# eagle_exp_3.net
KiCad netlist of a schematic drawn in EAGLE
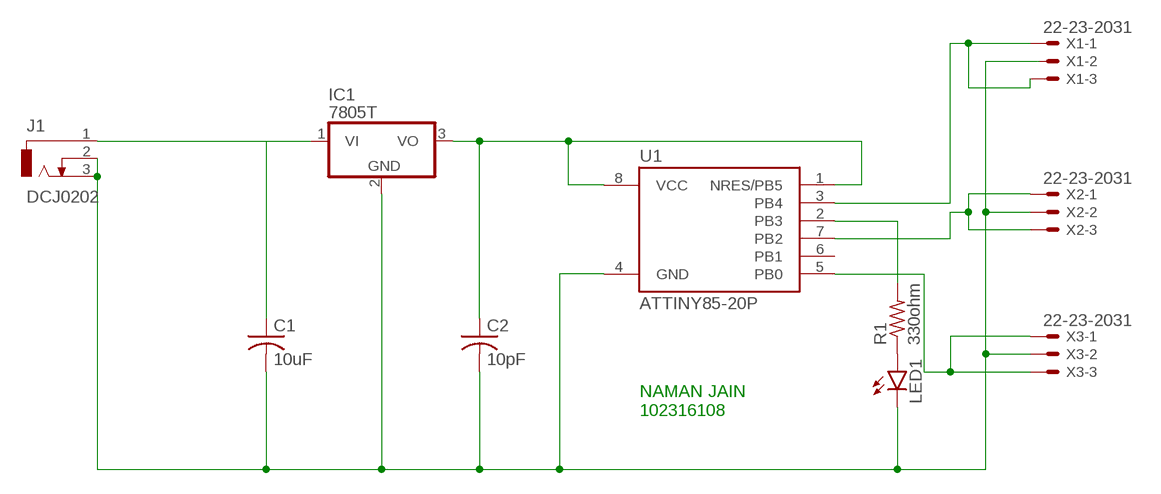
[diagram p0: schematic, sheet 1]

(export (version "E")
  (design (tool "Eeschema 10.0.6"))
  (components
    (comp (ref "C1")
      (value "10uF")
      (footprint "eagle-import:C025-024X044")
      (libsource (lib "eagle-import") (part "C-US025-024X044"))
    )
    (comp (ref "C2")
      (value "10pF")
      (footprint "eagle-import:C025-024X044")
      (libsource (lib "eagle-import") (part "C-US025-024X044"))
    )
    (comp (ref "IC1")
      (value "7805T")
      (footprint "eagle-import:TO220H")
      (libsource (lib "eagle-import") (part "78T05"))
    )
    (comp (ref "J1")
      (value "DCJ0202")
      (footprint "eagle-import:DCJ0202")
      (libsource (lib "eagle-import") (part "DCJ0202"))
    )
    (comp (ref "LED1")
      (value "LED3MM")
      (footprint "eagle-import:LED3MM")
      (libsource (lib "eagle-import") (part "LED3MM"))
    )
    (comp (ref "R1")
      (value "330ohm")
      (footprint "eagle-import:0207_5V")
      (libsource (lib "eagle-import") (part "R-US_0207/5V"))
    )
    (comp (ref "U1")
      (value "ATTINY85-20P")
      (footprint "eagle-import:PDIP08_300MIL")
      (libsource (lib "eagle-import") (part "ATTINY85P-20"))
    )
    (comp (ref "X1")
      (value "22-23-2031")
      (footprint "eagle-import:22-23-2031")
      (fields (field (name "MF") "MOLEX"))
      (libsource (lib "eagle-import") (part "22-23-2031"))
    )
    (comp (ref "X2")
      (value "22-23-2031")
      (footprint "eagle-import:22-23-2031")
      (fields (field (name "MF") "MOLEX"))
      (libsource (lib "eagle-import") (part "22-23-2031"))
    )
    (comp (ref "X3")
      (value "22-23-2031")
      (footprint "eagle-import:22-23-2031")
      (fields (field (name "MF") "MOLEX"))
      (libsource (lib "eagle-import") (part "22-23-2031"))
    )
  )
  (nets
    (net (code "1") (name "Net-(IC1-GND)") (class "Default")
      (node (ref "C1") (pin "2") (pinfunction "2_2") (pintype "passive"))
      (node (ref "C2") (pin "2") (pinfunction "2_2") (pintype "passive"))
      (node (ref "IC1") (pin "2") (pinfunction "GND_2") (pintype "passive"))
      (node (ref "J1") (pin "2") (pinfunction "2_2") (pintype "passive"))
      (node (ref "J1") (pin "3") (pinfunction "3_3") (pintype "passive"))
      (node (ref "LED1") (pin "K") (pinfunction "C_K") (pintype "passive"))
      (node (ref "U1") (pin "4") (pinfunction "GND_4") (pintype "power_in"))
      (node (ref "X1") (pin "2") (pinfunction "S_2") (pintype "passive"))
      (node (ref "X2") (pin "2") (pinfunction "S_2") (pintype "passive"))
      (node (ref "X3") (pin "2") (pinfunction "S_2") (pintype "passive"))
    )
    (net (code "2") (name "Net-(IC1-VI)") (class "Default")
      (node (ref "IC1") (pin "1") (pinfunction "VI_1") (pintype "input"))
      (node (ref "J1") (pin "1") (pinfunction "1_1") (pintype "passive"))
    )
    (net (code "3") (name "Net-(IC1-VO)") (class "Default")
      (node (ref "C2") (pin "1") (pinfunction "1_1") (pintype "passive"))
      (node (ref "IC1") (pin "3") (pinfunction "VO_3") (pintype "passive"))
      (node (ref "U1") (pin "1") (pinfunction "NRES/PB5_1") (pintype "bidirectional"))
      (node (ref "U1") (pin "8") (pinfunction "VCC_8") (pintype "power_in"))
    )
    (net (code "4") (name "Net-(LED1-PadA)") (class "Default")
      (node (ref "LED1") (pin "A") (pinfunction "A_A") (pintype "passive"))
      (node (ref "R1") (pin "1") (pinfunction "1_1") (pintype "passive"))
    )
    (net (code "5") (name "Net-(U1-PB0)") (class "Default")
      (node (ref "U1") (pin "5") (pinfunction "PB0_5") (pintype "bidirectional"))
      (node (ref "X3") (pin "1") (pinfunction "S_1") (pintype "passive"))
      (node (ref "X3") (pin "3") (pinfunction "S_3") (pintype "passive"))
    )
    (net (code "6") (name "Net-(U1-PB2)") (class "Default")
      (node (ref "U1") (pin "7") (pinfunction "PB2_7") (pintype "bidirectional"))
      (node (ref "X2") (pin "1") (pinfunction "S_1") (pintype "passive"))
      (node (ref "X2") (pin "3") (pinfunction "S_3") (pintype "passive"))
    )
    (net (code "7") (name "Net-(U1-PB3)") (class "Default")
      (node (ref "R1") (pin "2") (pinfunction "2_2") (pintype "passive"))
      (node (ref "U1") (pin "2") (pinfunction "PB3_2") (pintype "bidirectional"))
    )
    (net (code "8") (name "Net-(U1-PB4)") (class "Default")
      (node (ref "U1") (pin "3") (pinfunction "PB4_3") (pintype "bidirectional"))
      (node (ref "X1") (pin "1") (pinfunction "S_1") (pintype "passive"))
      (node (ref "X1") (pin "3") (pinfunction "S_3") (pintype "passive"))
    )
    (net (code "9") (name "unconnected-(C1-Pad1)") (class "Default")
      (node (ref "C1") (pin "1") (pinfunction "1_1") (pintype "passive"))
    )
    (net (code "10") (name "unconnected-(U1-PB1-Pad6)") (class "Default")
      (node (ref "U1") (pin "6") (pinfunction "PB1_6") (pintype "bidirectional"))
    )
  )
)
